# mcu.net
KiCad netlist of a schematic drawn in Altium Designer
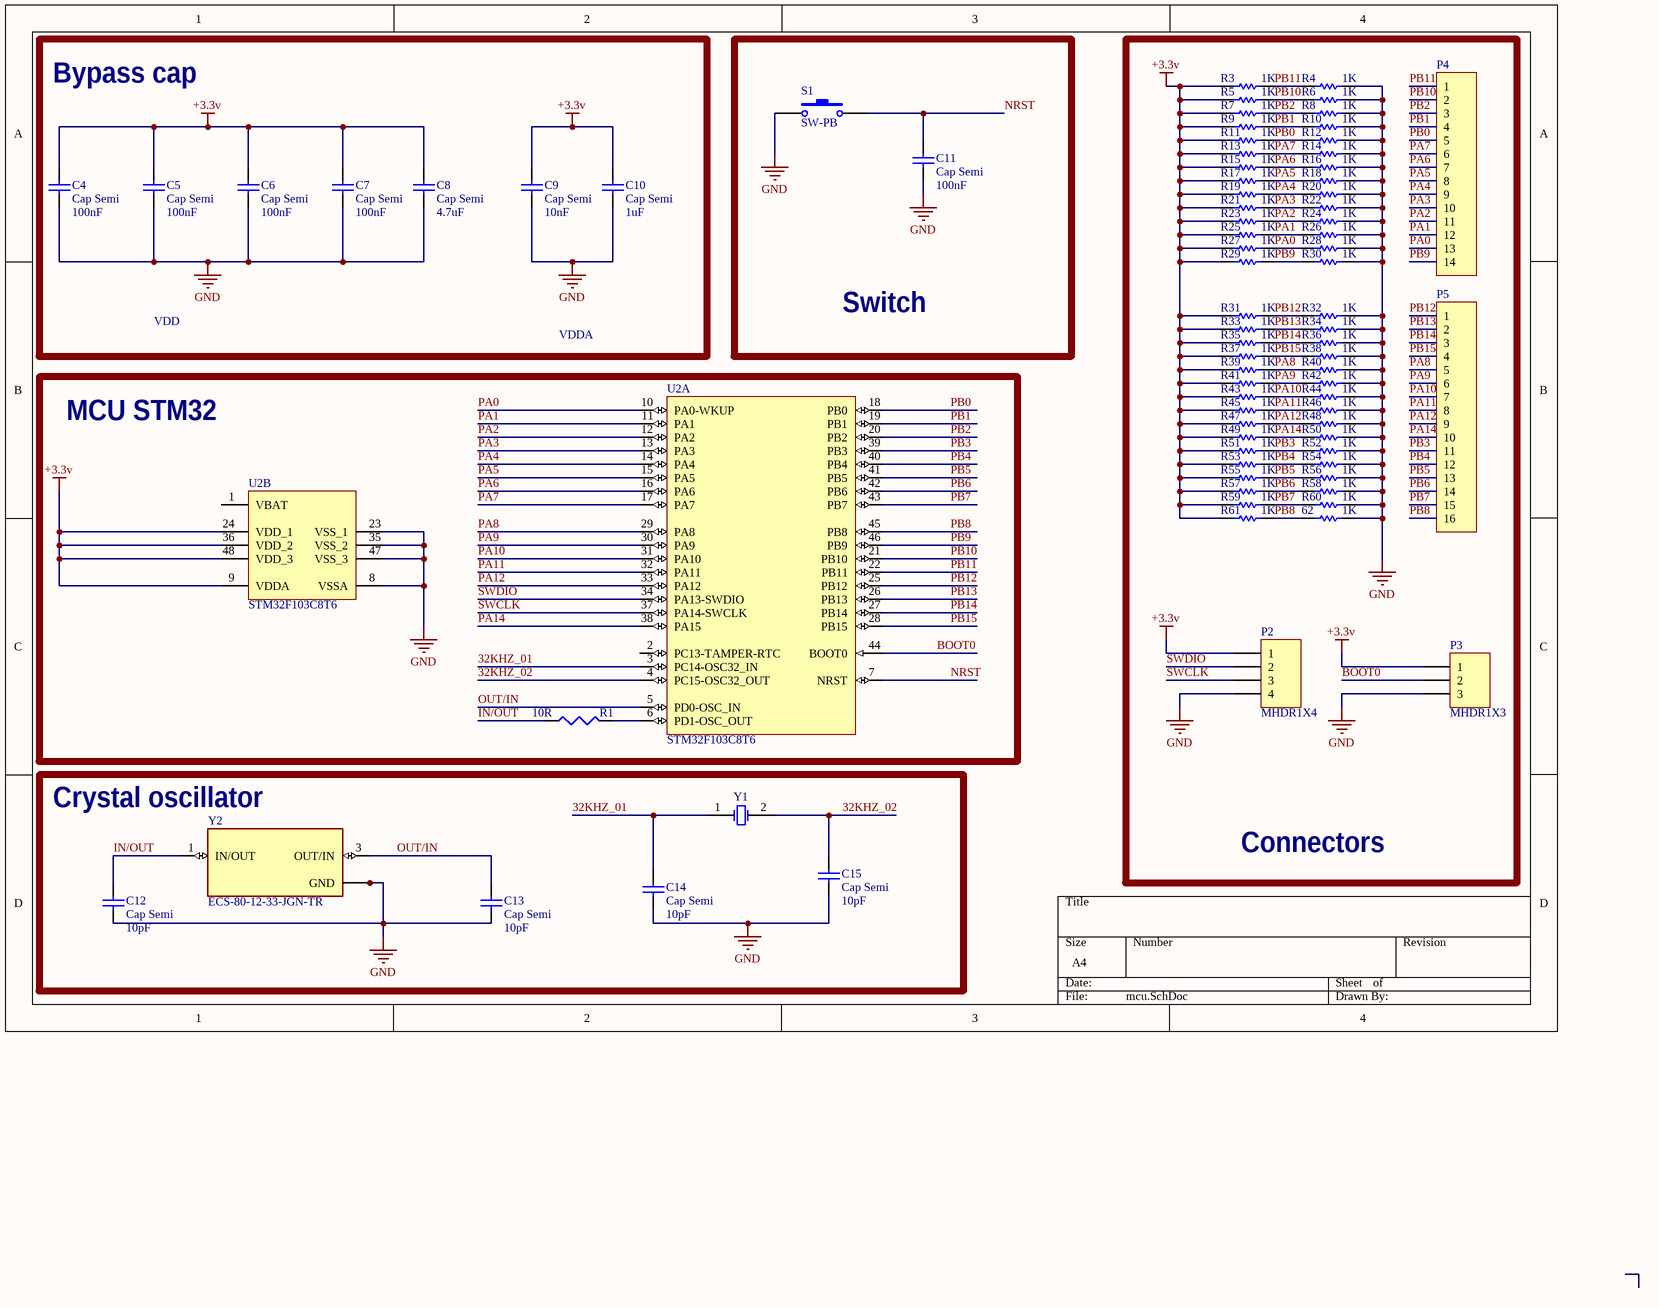
[diagram p0: mcu.SchDoc]

(export (version "E")
  (design (tool "Eeschema 10.0.6"))
  (components
    (comp (ref "62")
      (value "1K")
      (footprint "MY_0603")
      (description "Standard resistor")
      (fields (field (name "ASID PART NUMBER") "Res-AS"))
      (libsource (lib "1. Mylib Rev 4") (part "Res"))
    )
    (comp (ref "C4")
      (value "Cap Semi")
      (footprint "1608[0603]")
      (description "Capacitor (Semiconductor SIM Model)")
      (fields (field (name "ALTIUM_VALUE") "100nF") (field (name "PUBLISHER") "Altium Limited"))
      (libsource (lib "Miscellaneous Devices") (part "Cap Semi"))
    )
    (comp (ref "C5")
      (value "Cap Semi")
      (footprint "1608[0603]")
      (description "Capacitor (Semiconductor SIM Model)")
      (fields (field (name "ALTIUM_VALUE") "100nF") (field (name "PUBLISHER") "Altium Limited"))
      (libsource (lib "Miscellaneous Devices") (part "Cap Semi"))
    )
    (comp (ref "C6")
      (value "Cap Semi")
      (footprint "1608[0603]")
      (description "Capacitor (Semiconductor SIM Model)")
      (fields (field (name "ALTIUM_VALUE") "100nF") (field (name "PUBLISHER") "Altium Limited"))
      (libsource (lib "Miscellaneous Devices") (part "Cap Semi"))
    )
    (comp (ref "C7")
      (value "Cap Semi")
      (footprint "1608[0603]")
      (description "Capacitor (Semiconductor SIM Model)")
      (fields (field (name "ALTIUM_VALUE") "100nF") (field (name "PUBLISHER") "Altium Limited"))
      (libsource (lib "Miscellaneous Devices") (part "Cap Semi"))
    )
    (comp (ref "C8")
      (value "Cap Semi")
      (footprint "1608[0603]")
      (description "Capacitor (Semiconductor SIM Model)")
      (fields (field (name "ALTIUM_VALUE") "4.7uF") (field (name "PUBLISHER") "Altium Limited"))
      (libsource (lib "Miscellaneous Devices") (part "Cap Semi"))
    )
    (comp (ref "C9")
      (value "Cap Semi")
      (footprint "1608[0603]")
      (description "Capacitor (Semiconductor SIM Model)")
      (fields (field (name "ALTIUM_VALUE") "10nF") (field (name "PUBLISHER") "Altium Limited"))
      (libsource (lib "Miscellaneous Devices") (part "Cap Semi"))
    )
    (comp (ref "C10")
      (value "Cap Semi")
      (footprint "1608[0603]")
      (description "Capacitor (Semiconductor SIM Model)")
      (fields (field (name "ALTIUM_VALUE") "1uF") (field (name "PUBLISHER") "Altium Limited"))
      (libsource (lib "Miscellaneous Devices") (part "Cap Semi"))
    )
    (comp (ref "C11")
      (value "Cap Semi")
      (footprint "1608[0603]")
      (description "Capacitor (Semiconductor SIM Model)")
      (fields (field (name "ALTIUM_VALUE") "100nF") (field (name "PUBLISHER") "Altium Limited"))
      (libsource (lib "Miscellaneous Devices") (part "Cap Semi"))
    )
    (comp (ref "C12")
      (value "Cap Semi")
      (footprint "0402")
      (description "Capacitor (Semiconductor SIM Model)")
      (fields (field (name "ALTIUM_VALUE") "10pF") (field (name "PUBLISHER") "Altium Limited"))
      (libsource (lib "Miscellaneous Devices") (part "Cap Semi"))
    )
    (comp (ref "C13")
      (value "Cap Semi")
      (footprint "0402")
      (description "Capacitor (Semiconductor SIM Model)")
      (fields (field (name "ALTIUM_VALUE") "10pF") (field (name "PUBLISHER") "Altium Limited"))
      (libsource (lib "Miscellaneous Devices") (part "Cap Semi"))
    )
    (comp (ref "C14")
      (value "Cap Semi")
      (footprint "0402")
      (description "Capacitor (Semiconductor SIM Model)")
      (fields (field (name "ALTIUM_VALUE") "10pF") (field (name "PUBLISHER") "Altium Limited"))
      (libsource (lib "Miscellaneous Devices") (part "Cap Semi"))
    )
    (comp (ref "C15")
      (value "Cap Semi")
      (footprint "0402")
      (description "Capacitor (Semiconductor SIM Model)")
      (fields (field (name "ALTIUM_VALUE") "10pF") (field (name "PUBLISHER") "Altium Limited"))
      (libsource (lib "Miscellaneous Devices") (part "Cap Semi"))
    )
    (comp (ref "P2")
      (value "MHDR1X4")
      (footprint "MHDR1X4body")
      (description "Header, 4-Pin")
      (fields (field (name "PUBLISHER") "Altium Limited"))
      (libsource (lib "4. smartmcu") (part "MHDR1X4"))
    )
    (comp (ref "P3")
      (value "MHDR1X3")
      (footprint "MHDR1X3body")
      (description "Header, 3-Pin")
      (fields (field (name "PUBLISHER") "Altium Limited"))
      (libsource (lib "4. smartmcu") (part "MHDR1X3"))
    )
    (comp (ref "P4")
      (value "Header 14")
      (footprint "MY_FE14")
      (description "Header, 14-Pin")
      (fields (field (name "ASID PART NUMBER") "Header 14-AS"))
      (libsource (lib "1. Mylib Rev 4") (part "Header 14"))
    )
    (comp (ref "P5")
      (value "Header 16")
      (footprint "MY_FE16")
      (description "Header, 16-Pin")
      (fields (field (name "ASID PART NUMBER") "Header 16-AS"))
      (libsource (lib "1. Mylib Rev 4") (part "Header 16"))
    )
    (comp (ref "R1")
      (value "10R")
      (footprint "J1-0603")
      (description "Resistor")
      (fields (field (name "Comment") "Res3") (field (name "PUBLISHER") "Altium Limited"))
      (libsource (lib "Miscellaneous Devices") (part "Res3"))
    )
    (comp (ref "R3")
      (value "1K")
      (footprint "MY_0603")
      (description "Standard resistor")
      (fields (field (name "ASID PART NUMBER") "Res-AS"))
      (libsource (lib "1. Mylib Rev 4") (part "Res"))
    )
    (comp (ref "R4")
      (value "1K")
      (footprint "MY_0603")
      (description "Standard resistor")
      (fields (field (name "ASID PART NUMBER") "Res-AS"))
      (libsource (lib "1. Mylib Rev 4") (part "Res"))
    )
    (comp (ref "R5")
      (value "1K")
      (footprint "MY_0603")
      (description "Standard resistor")
      (fields (field (name "ASID PART NUMBER") "Res-AS"))
      (libsource (lib "1. Mylib Rev 4") (part "Res"))
    )
    (comp (ref "R6")
      (value "1K")
      (footprint "MY_0603")
      (description "Standard resistor")
      (fields (field (name "ASID PART NUMBER") "Res-AS"))
      (libsource (lib "1. Mylib Rev 4") (part "Res"))
    )
    (comp (ref "R7")
      (value "1K")
      (footprint "MY_0603")
      (description "Standard resistor")
      (fields (field (name "ASID PART NUMBER") "Res-AS"))
      (libsource (lib "1. Mylib Rev 4") (part "Res"))
    )
    (comp (ref "R8")
      (value "1K")
      (footprint "MY_0603")
      (description "Standard resistor")
      (fields (field (name "ASID PART NUMBER") "Res-AS"))
      (libsource (lib "1. Mylib Rev 4") (part "Res"))
    )
    (comp (ref "R9")
      (value "1K")
      (footprint "MY_0603")
      (description "Standard resistor")
      (fields (field (name "ASID PART NUMBER") "Res-AS"))
      (libsource (lib "1. Mylib Rev 4") (part "Res"))
    )
    (comp (ref "R10")
      (value "1K")
      (footprint "MY_0603")
      (description "Standard resistor")
      (fields (field (name "ASID PART NUMBER") "Res-AS"))
      (libsource (lib "1. Mylib Rev 4") (part "Res"))
    )
    (comp (ref "R11")
      (value "1K")
      (footprint "MY_0603")
      (description "Standard resistor")
      (fields (field (name "ASID PART NUMBER") "Res-AS"))
      (libsource (lib "1. Mylib Rev 4") (part "Res"))
    )
    (comp (ref "R12")
      (value "1K")
      (footprint "MY_0603")
      (description "Standard resistor")
      (fields (field (name "ASID PART NUMBER") "Res-AS"))
      (libsource (lib "1. Mylib Rev 4") (part "Res"))
    )
    (comp (ref "R13")
      (value "1K")
      (footprint "MY_0603")
      (description "Standard resistor")
      (fields (field (name "ASID PART NUMBER") "Res-AS"))
      (libsource (lib "1. Mylib Rev 4") (part "Res"))
    )
    (comp (ref "R14")
      (value "1K")
      (footprint "MY_0603")
      (description "Standard resistor")
      (fields (field (name "ASID PART NUMBER") "Res-AS"))
      (libsource (lib "1. Mylib Rev 4") (part "Res"))
    )
    (comp (ref "R15")
      (value "1K")
      (footprint "MY_0603")
      (description "Standard resistor")
      (fields (field (name "ASID PART NUMBER") "Res-AS"))
      (libsource (lib "1. Mylib Rev 4") (part "Res"))
    )
    (comp (ref "R16")
      (value "1K")
      (footprint "MY_0603")
      (description "Standard resistor")
      (fields (field (name "ASID PART NUMBER") "Res-AS"))
      (libsource (lib "1. Mylib Rev 4") (part "Res"))
    )
    (comp (ref "R17")
      (value "1K")
      (footprint "MY_0603")
      (description "Standard resistor")
      (fields (field (name "ASID PART NUMBER") "Res-AS"))
      (libsource (lib "1. Mylib Rev 4") (part "Res"))
    )
    (comp (ref "R18")
      (value "1K")
      (footprint "MY_0603")
      (description "Standard resistor")
      (fields (field (name "ASID PART NUMBER") "Res-AS"))
      (libsource (lib "1. Mylib Rev 4") (part "Res"))
    )
    (comp (ref "R19")
      (value "1K")
      (footprint "MY_0603")
      (description "Standard resistor")
      (fields (field (name "ASID PART NUMBER") "Res-AS"))
      (libsource (lib "1. Mylib Rev 4") (part "Res"))
    )
    (comp (ref "R20")
      (value "1K")
      (footprint "MY_0603")
      (description "Standard resistor")
      (fields (field (name "ASID PART NUMBER") "Res-AS"))
      (libsource (lib "1. Mylib Rev 4") (part "Res"))
    )
    (comp (ref "R21")
      (value "1K")
      (footprint "MY_0603")
      (description "Standard resistor")
      (fields (field (name "ASID PART NUMBER") "Res-AS"))
      (libsource (lib "1. Mylib Rev 4") (part "Res"))
    )
    (comp (ref "R22")
      (value "1K")
      (footprint "MY_0603")
      (description "Standard resistor")
      (fields (field (name "ASID PART NUMBER") "Res-AS"))
      (libsource (lib "1. Mylib Rev 4") (part "Res"))
    )
    (comp (ref "R23")
      (value "1K")
      (footprint "MY_0603")
      (description "Standard resistor")
      (fields (field (name "ASID PART NUMBER") "Res-AS"))
      (libsource (lib "1. Mylib Rev 4") (part "Res"))
    )
    (comp (ref "R24")
      (value "1K")
      (footprint "MY_0603")
      (description "Standard resistor")
      (fields (field (name "ASID PART NUMBER") "Res-AS"))
      (libsource (lib "1. Mylib Rev 4") (part "Res"))
    )
    (comp (ref "R25")
      (value "1K")
      (footprint "MY_0603")
      (description "Standard resistor")
      (fields (field (name "ASID PART NUMBER") "Res-AS"))
      (libsource (lib "1. Mylib Rev 4") (part "Res"))
    )
    (comp (ref "R26")
      (value "1K")
      (footprint "MY_0603")
      (description "Standard resistor")
      (fields (field (name "ASID PART NUMBER") "Res-AS"))
      (libsource (lib "1. Mylib Rev 4") (part "Res"))
    )
    (comp (ref "R27")
      (value "1K")
      (footprint "MY_0603")
      (description "Standard resistor")
      (fields (field (name "ASID PART NUMBER") "Res-AS"))
      (libsource (lib "1. Mylib Rev 4") (part "Res"))
    )
    (comp (ref "R28")
      (value "1K")
      (footprint "MY_0603")
      (description "Standard resistor")
      (fields (field (name "ASID PART NUMBER") "Res-AS"))
      (libsource (lib "1. Mylib Rev 4") (part "Res"))
    )
    (comp (ref "R29")
      (value "1K")
      (footprint "MY_0603")
      (description "Standard resistor")
      (fields (field (name "ASID PART NUMBER") "Res-AS"))
      (libsource (lib "1. Mylib Rev 4") (part "Res"))
    )
    (comp (ref "R30")
      (value "1K")
      (footprint "MY_0603")
      (description "Standard resistor")
      (fields (field (name "ASID PART NUMBER") "Res-AS"))
      (libsource (lib "1. Mylib Rev 4") (part "Res"))
    )
    (comp (ref "R31")
      (value "1K")
      (footprint "MY_0603")
      (description "Standard resistor")
      (fields (field (name "ASID PART NUMBER") "Res-AS"))
      (libsource (lib "1. Mylib Rev 4") (part "Res"))
    )
    (comp (ref "R32")
      (value "1K")
      (footprint "MY_0603")
      (description "Standard resistor")
      (fields (field (name "ASID PART NUMBER") "Res-AS"))
      (libsource (lib "1. Mylib Rev 4") (part "Res"))
    )
    (comp (ref "R33")
      (value "1K")
      (footprint "MY_0603")
      (description "Standard resistor")
      (fields (field (name "ASID PART NUMBER") "Res-AS"))
      (libsource (lib "1. Mylib Rev 4") (part "Res"))
    )
    (comp (ref "R34")
      (value "1K")
      (footprint "MY_0603")
      (description "Standard resistor")
      (fields (field (name "ASID PART NUMBER") "Res-AS"))
      (libsource (lib "1. Mylib Rev 4") (part "Res"))
    )
    (comp (ref "R35")
      (value "1K")
      (footprint "MY_0603")
      (description "Standard resistor")
      (fields (field (name "ASID PART NUMBER") "Res-AS"))
      (libsource (lib "1. Mylib Rev 4") (part "Res"))
    )
    (comp (ref "R36")
      (value "1K")
      (footprint "MY_0603")
      (description "Standard resistor")
      (fields (field (name "ASID PART NUMBER") "Res-AS"))
      (libsource (lib "1. Mylib Rev 4") (part "Res"))
    )
    (comp (ref "R37")
      (value "1K")
      (footprint "MY_0603")
      (description "Standard resistor")
      (fields (field (name "ASID PART NUMBER") "Res-AS"))
      (libsource (lib "1. Mylib Rev 4") (part "Res"))
    )
    (comp (ref "R38")
      (value "1K")
      (footprint "MY_0603")
      (description "Standard resistor")
      (fields (field (name "ASID PART NUMBER") "Res-AS"))
      (libsource (lib "1. Mylib Rev 4") (part "Res"))
    )
    (comp (ref "R39")
      (value "1K")
      (footprint "MY_0603")
      (description "Standard resistor")
      (fields (field (name "ASID PART NUMBER") "Res-AS"))
      (libsource (lib "1. Mylib Rev 4") (part "Res"))
    )
    (comp (ref "R40")
      (value "1K")
      (footprint "MY_0603")
      (description "Standard resistor")
      (fields (field (name "ASID PART NUMBER") "Res-AS"))
      (libsource (lib "1. Mylib Rev 4") (part "Res"))
    )
    (comp (ref "R41")
      (value "1K")
      (footprint "MY_0603")
      (description "Standard resistor")
      (fields (field (name "ASID PART NUMBER") "Res-AS"))
      (libsource (lib "1. Mylib Rev 4") (part "Res"))
    )
    (comp (ref "R42")
      (value "1K")
      (footprint "MY_0603")
      (description "Standard resistor")
      (fields (field (name "ASID PART NUMBER") "Res-AS"))
      (libsource (lib "1. Mylib Rev 4") (part "Res"))
    )
    (comp (ref "R43")
      (value "1K")
      (footprint "MY_0603")
      (description "Standard resistor")
      (fields (field (name "ASID PART NUMBER") "Res-AS"))
      (libsource (lib "1. Mylib Rev 4") (part "Res"))
    )
    (comp (ref "R44")
      (value "1K")
      (footprint "MY_0603")
      (description "Standard resistor")
      (fields (field (name "ASID PART NUMBER") "Res-AS"))
      (libsource (lib "1. Mylib Rev 4") (part "Res"))
    )
    (comp (ref "R45")
      (value "1K")
      (footprint "MY_0603")
      (description "Standard resistor")
      (fields (field (name "ASID PART NUMBER") "Res-AS"))
      (libsource (lib "1. Mylib Rev 4") (part "Res"))
    )
    (comp (ref "R46")
      (value "1K")
      (footprint "MY_0603")
      (description "Standard resistor")
      (fields (field (name "ASID PART NUMBER") "Res-AS"))
      (libsource (lib "1. Mylib Rev 4") (part "Res"))
    )
    (comp (ref "R47")
      (value "1K")
      (footprint "MY_0603")
      (description "Standard resistor")
      (fields (field (name "ASID PART NUMBER") "Res-AS"))
      (libsource (lib "1. Mylib Rev 4") (part "Res"))
    )
    (comp (ref "R48")
      (value "1K")
      (footprint "MY_0603")
      (description "Standard resistor")
      (fields (field (name "ASID PART NUMBER") "Res-AS"))
      (libsource (lib "1. Mylib Rev 4") (part "Res"))
    )
    (comp (ref "R49")
      (value "1K")
      (footprint "MY_0603")
      (description "Standard resistor")
      (fields (field (name "ASID PART NUMBER") "Res-AS"))
      (libsource (lib "1. Mylib Rev 4") (part "Res"))
    )
    (comp (ref "R50")
      (value "1K")
      (footprint "MY_0603")
      (description "Standard resistor")
      (fields (field (name "ASID PART NUMBER") "Res-AS"))
      (libsource (lib "1. Mylib Rev 4") (part "Res"))
    )
    (comp (ref "R51")
      (value "1K")
      (footprint "MY_0603")
      (description "Standard resistor")
      (fields (field (name "ASID PART NUMBER") "Res-AS"))
      (libsource (lib "1. Mylib Rev 4") (part "Res"))
    )
    (comp (ref "R52")
      (value "1K")
      (footprint "MY_0603")
      (description "Standard resistor")
      (fields (field (name "ASID PART NUMBER") "Res-AS"))
      (libsource (lib "1. Mylib Rev 4") (part "Res"))
    )
    (comp (ref "R53")
      (value "1K")
      (footprint "MY_0603")
      (description "Standard resistor")
      (fields (field (name "ASID PART NUMBER") "Res-AS"))
      (libsource (lib "1. Mylib Rev 4") (part "Res"))
    )
    (comp (ref "R54")
      (value "1K")
      (footprint "MY_0603")
      (description "Standard resistor")
      (fields (field (name "ASID PART NUMBER") "Res-AS"))
      (libsource (lib "1. Mylib Rev 4") (part "Res"))
    )
    (comp (ref "R55")
      (value "1K")
      (footprint "MY_0603")
      (description "Standard resistor")
      (fields (field (name "ASID PART NUMBER") "Res-AS"))
      (libsource (lib "1. Mylib Rev 4") (part "Res"))
    )
    (comp (ref "R56")
      (value "1K")
      (footprint "MY_0603")
      (description "Standard resistor")
      (fields (field (name "ASID PART NUMBER") "Res-AS"))
      (libsource (lib "1. Mylib Rev 4") (part "Res"))
    )
    (comp (ref "R57")
      (value "1K")
      (footprint "MY_0603")
      (description "Standard resistor")
      (fields (field (name "ASID PART NUMBER") "Res-AS"))
      (libsource (lib "1. Mylib Rev 4") (part "Res"))
    )
    (comp (ref "R58")
      (value "1K")
      (footprint "MY_0603")
      (description "Standard resistor")
      (fields (field (name "ASID PART NUMBER") "Res-AS"))
      (libsource (lib "1. Mylib Rev 4") (part "Res"))
    )
    (comp (ref "R59")
      (value "1K")
      (footprint "MY_0603")
      (description "Standard resistor")
      (fields (field (name "ASID PART NUMBER") "Res-AS"))
      (libsource (lib "1. Mylib Rev 4") (part "Res"))
    )
    (comp (ref "R60")
      (value "1K")
      (footprint "MY_0603")
      (description "Standard resistor")
      (fields (field (name "ASID PART NUMBER") "Res-AS"))
      (libsource (lib "1. Mylib Rev 4") (part "Res"))
    )
    (comp (ref "R61")
      (value "1K")
      (footprint "MY_0603")
      (description "Standard resistor")
      (fields (field (name "ASID PART NUMBER") "Res-AS"))
      (libsource (lib "1. Mylib Rev 4") (part "Res"))
    )
    (comp (ref "S1")
      (value "SW-PB")
      (footprint "SPST-2")
      (description "Switch")
      (fields (field (name "PUBLISHER") "Altium Limited"))
      (libsource (lib "Miscellaneous Devices") (part "SW-PB"))
    )
    (comp (ref "U2")
      (value "STM32F103C8T6")
      (footprint "STM-LQFP48_N")
      (libsource (lib "4. smartmcu") (part "STM32F103C8T6"))
    )
    (comp (ref "Y1")
      (value "~")
      (footprint "R38")
      (description "Crystal Oscillator")
      (fields (field (name "PUBLISHER") "Altium Limited"))
      (libsource (lib "Miscellaneous Devices") (part "XTAL"))
    )
    (comp (ref "Y2")
      (value "ECS-80-12-33-JGN-TR")
      (footprint "8MHZCrystall")
      (description "8MHz Â±20ppm Crystal 12pF 400 Ohms 4-SMD, No Lead")
      (fields
        (field (name "MF") "ECS Inc.")
        (field (name "BUYPART") "https://www.snapeda.com/parts/ECS-80-12-33-JGN-TR/ECS%20Inc./view-part/4477300/?ref=eda")
      )
      (libsource (lib "1. smartmcu") (part "ECS-80-12-33-JGN-TR"))
    )
  )
  (nets
    (net (code "1") (name "+3.3v") (class "Default")
      (node (ref "C10") (pin "2") (pinfunction "2_2") (pintype "passive"))
      (node (ref "C4") (pin "2") (pinfunction "2_2") (pintype "passive"))
      (node (ref "C5") (pin "2") (pinfunction "2_2") (pintype "passive"))
      (node (ref "C6") (pin "2") (pinfunction "2_2") (pintype "passive"))
      (node (ref "C7") (pin "2") (pinfunction "2_2") (pintype "passive"))
      (node (ref "C8") (pin "2") (pinfunction "2_2") (pintype "passive"))
      (node (ref "C9") (pin "2") (pinfunction "2_2") (pintype "passive"))
      (node (ref "P2") (pin "1") (pinfunction "1_1") (pintype "passive"))
      (node (ref "P3") (pin "1") (pinfunction "1_1") (pintype "passive"))
      (node (ref "R11") (pin "1") (pinfunction "1_1") (pintype "passive"))
      (node (ref "R13") (pin "1") (pinfunction "1_1") (pintype "passive"))
      (node (ref "R15") (pin "1") (pinfunction "1_1") (pintype "passive"))
      (node (ref "R17") (pin "1") (pinfunction "1_1") (pintype "passive"))
      (node (ref "R19") (pin "1") (pinfunction "1_1") (pintype "passive"))
      (node (ref "R21") (pin "1") (pinfunction "1_1") (pintype "passive"))
      (node (ref "R23") (pin "1") (pinfunction "1_1") (pintype "passive"))
      (node (ref "R25") (pin "1") (pinfunction "1_1") (pintype "passive"))
      (node (ref "R27") (pin "1") (pinfunction "1_1") (pintype "passive"))
      (node (ref "R29") (pin "1") (pinfunction "1_1") (pintype "passive"))
      (node (ref "R3") (pin "1") (pinfunction "1_1") (pintype "passive"))
      (node (ref "R31") (pin "1") (pinfunction "1_1") (pintype "passive"))
      (node (ref "R33") (pin "1") (pinfunction "1_1") (pintype "passive"))
      (node (ref "R35") (pin "1") (pinfunction "1_1") (pintype "passive"))
      (node (ref "R37") (pin "1") (pinfunction "1_1") (pintype "passive"))
      (node (ref "R39") (pin "1") (pinfunction "1_1") (pintype "passive"))
      (node (ref "R41") (pin "1") (pinfunction "1_1") (pintype "passive"))
      (node (ref "R43") (pin "1") (pinfunction "1_1") (pintype "passive"))
      (node (ref "R45") (pin "1") (pinfunction "1_1") (pintype "passive"))
      (node (ref "R47") (pin "1") (pinfunction "1_1") (pintype "passive"))
      (node (ref "R49") (pin "1") (pinfunction "1_1") (pintype "passive"))
      (node (ref "R5") (pin "1") (pinfunction "1_1") (pintype "passive"))
      (node (ref "R51") (pin "1") (pinfunction "1_1") (pintype "passive"))
      (node (ref "R53") (pin "1") (pinfunction "1_1") (pintype "passive"))
      (node (ref "R55") (pin "1") (pinfunction "1_1") (pintype "passive"))
      (node (ref "R57") (pin "1") (pinfunction "1_1") (pintype "passive"))
      (node (ref "R59") (pin "1") (pinfunction "1_1") (pintype "passive"))
      (node (ref "R61") (pin "1") (pinfunction "1_1") (pintype "passive"))
      (node (ref "R7") (pin "1") (pinfunction "1_1") (pintype "passive"))
      (node (ref "R9") (pin "1") (pinfunction "1_1") (pintype "passive"))
      (node (ref "U2") (pin "24") (pinfunction "VDD_1_24") (pintype "power_in"))
      (node (ref "U2") (pin "36") (pinfunction "VDD_2_36") (pintype "power_in"))
      (node (ref "U2") (pin "48") (pinfunction "VDD_3_48") (pintype "power_in"))
      (node (ref "U2") (pin "9") (pinfunction "VDDA_9") (pintype "power_in"))
    )
    (net (code "2") (name "/32KHZ_01") (class "Default")
      (node (ref "C14") (pin "2") (pinfunction "2_2") (pintype "passive"))
      (node (ref "U2") (pin "3") (pinfunction "PC14-OSC32_IN_3") (pintype "bidirectional"))
      (node (ref "Y1") (pin "1") (pinfunction "OSC1_1") (pintype "passive"))
    )
    (net (code "3") (name "/32KHZ_02") (class "Default")
      (node (ref "C15") (pin "2") (pinfunction "2_2") (pintype "passive"))
      (node (ref "U2") (pin "4") (pinfunction "PC15-OSC32_OUT_4") (pintype "bidirectional"))
      (node (ref "Y1") (pin "2") (pinfunction "OSC2_2") (pintype "passive"))
    )
    (net (code "4") (name "/BOOT0") (class "Default")
      (node (ref "P3") (pin "2") (pinfunction "2_2") (pintype "passive"))
      (node (ref "U2") (pin "44") (pinfunction "BOOT0_44") (pintype "input"))
    )
    (net (code "5") (name "/IN{slash}OUT") (class "Default")
      (node (ref "C12") (pin "2") (pinfunction "2_2") (pintype "passive"))
      (node (ref "R1") (pin "1") (pinfunction "1_1") (pintype "passive"))
      (node (ref "Y2") (pin "1") (pinfunction "IN/OUT_1") (pintype "bidirectional"))
    )
    (net (code "6") (name "/NRST") (class "Default")
      (node (ref "C11") (pin "2") (pinfunction "2_2") (pintype "passive"))
      (node (ref "S1") (pin "2") (pinfunction "2_2") (pintype "passive"))
      (node (ref "U2") (pin "7") (pinfunction "NRST_7") (pintype "bidirectional"))
    )
    (net (code "7") (name "/OUT{slash}IN") (class "Default")
      (node (ref "C13") (pin "2") (pinfunction "2_2") (pintype "passive"))
      (node (ref "U2") (pin "5") (pinfunction "PD0-OSC_IN_5") (pintype "bidirectional"))
      (node (ref "Y2") (pin "3") (pinfunction "OUT/IN_3") (pintype "bidirectional"))
    )
    (net (code "8") (name "/PA0") (class "Default")
      (node (ref "P4") (pin "13") (pinfunction "13_13") (pintype "passive"))
      (node (ref "R27") (pin "2") (pinfunction "2_2") (pintype "passive"))
      (node (ref "R28") (pin "1") (pinfunction "1_1") (pintype "passive"))
      (node (ref "U2") (pin "10") (pinfunction "PA0-WKUP_10") (pintype "bidirectional"))
    )
    (net (code "9") (name "/PA1") (class "Default")
      (node (ref "P4") (pin "12") (pinfunction "12_12") (pintype "passive"))
      (node (ref "R25") (pin "2") (pinfunction "2_2") (pintype "passive"))
      (node (ref "R26") (pin "1") (pinfunction "1_1") (pintype "passive"))
      (node (ref "U2") (pin "11") (pinfunction "PA1_11") (pintype "bidirectional"))
    )
    (net (code "10") (name "/PA2") (class "Default")
      (node (ref "P4") (pin "11") (pinfunction "11_11") (pintype "passive"))
      (node (ref "R23") (pin "2") (pinfunction "2_2") (pintype "passive"))
      (node (ref "R24") (pin "1") (pinfunction "1_1") (pintype "passive"))
      (node (ref "U2") (pin "12") (pinfunction "PA2_12") (pintype "bidirectional"))
    )
    (net (code "11") (name "/PA3") (class "Default")
      (node (ref "P4") (pin "10") (pinfunction "10_10") (pintype "passive"))
      (node (ref "R21") (pin "2") (pinfunction "2_2") (pintype "passive"))
      (node (ref "R22") (pin "1") (pinfunction "1_1") (pintype "passive"))
      (node (ref "U2") (pin "13") (pinfunction "PA3_13") (pintype "bidirectional"))
    )
    (net (code "12") (name "/PA4") (class "Default")
      (node (ref "P4") (pin "9") (pinfunction "9_9") (pintype "passive"))
      (node (ref "R19") (pin "2") (pinfunction "2_2") (pintype "passive"))
      (node (ref "R20") (pin "1") (pinfunction "1_1") (pintype "passive"))
      (node (ref "U2") (pin "14") (pinfunction "PA4_14") (pintype "bidirectional"))
    )
    (net (code "13") (name "/PA5") (class "Default")
      (node (ref "P4") (pin "8") (pinfunction "8_8") (pintype "passive"))
      (node (ref "R17") (pin "2") (pinfunction "2_2") (pintype "passive"))
      (node (ref "R18") (pin "1") (pinfunction "1_1") (pintype "passive"))
      (node (ref "U2") (pin "15") (pinfunction "PA5_15") (pintype "bidirectional"))
    )
    (net (code "14") (name "/PA6") (class "Default")
      (node (ref "P4") (pin "7") (pinfunction "7_7") (pintype "passive"))
      (node (ref "R15") (pin "2") (pinfunction "2_2") (pintype "passive"))
      (node (ref "R16") (pin "1") (pinfunction "1_1") (pintype "passive"))
      (node (ref "U2") (pin "16") (pinfunction "PA6_16") (pintype "bidirectional"))
    )
    (net (code "15") (name "/PA7") (class "Default")
      (node (ref "P4") (pin "6") (pinfunction "6_6") (pintype "passive"))
      (node (ref "R13") (pin "2") (pinfunction "2_2") (pintype "passive"))
      (node (ref "R14") (pin "1") (pinfunction "1_1") (pintype "passive"))
      (node (ref "U2") (pin "17") (pinfunction "PA7_17") (pintype "bidirectional"))
    )
    (net (code "16") (name "/PA8") (class "Default")
      (node (ref "P5") (pin "5") (pinfunction "5_5") (pintype "passive"))
      (node (ref "R39") (pin "2") (pinfunction "2_2") (pintype "passive"))
      (node (ref "R40") (pin "1") (pinfunction "1_1") (pintype "passive"))
      (node (ref "U2") (pin "29") (pinfunction "PA8_29") (pintype "bidirectional"))
    )
    (net (code "17") (name "/PA9") (class "Default")
      (node (ref "P5") (pin "6") (pinfunction "6_6") (pintype "passive"))
      (node (ref "R41") (pin "2") (pinfunction "2_2") (pintype "passive"))
      (node (ref "R42") (pin "1") (pinfunction "1_1") (pintype "passive"))
      (node (ref "U2") (pin "30") (pinfunction "PA9_30") (pintype "bidirectional"))
    )
    (net (code "18") (name "/PA10") (class "Default")
      (node (ref "P5") (pin "7") (pinfunction "7_7") (pintype "passive"))
      (node (ref "R43") (pin "2") (pinfunction "2_2") (pintype "passive"))
      (node (ref "R44") (pin "1") (pinfunction "1_1") (pintype "passive"))
      (node (ref "U2") (pin "31") (pinfunction "PA10_31") (pintype "bidirectional"))
    )
    (net (code "19") (name "/PA11") (class "Default")
      (node (ref "P5") (pin "8") (pinfunction "8_8") (pintype "passive"))
      (node (ref "R45") (pin "2") (pinfunction "2_2") (pintype "passive"))
      (node (ref "R46") (pin "1") (pinfunction "1_1") (pintype "passive"))
      (node (ref "U2") (pin "32") (pinfunction "PA11_32") (pintype "bidirectional"))
    )
    (net (code "20") (name "/PA12") (class "Default")
      (node (ref "P5") (pin "9") (pinfunction "9_9") (pintype "passive"))
      (node (ref "R47") (pin "2") (pinfunction "2_2") (pintype "passive"))
      (node (ref "R48") (pin "1") (pinfunction "1_1") (pintype "passive"))
      (node (ref "U2") (pin "33") (pinfunction "PA12_33") (pintype "bidirectional"))
    )
    (net (code "21") (name "/PA14") (class "Default")
      (node (ref "P5") (pin "10") (pinfunction "10_10") (pintype "passive"))
      (node (ref "R49") (pin "2") (pinfunction "2_2") (pintype "passive"))
      (node (ref "R50") (pin "1") (pinfunction "1_1") (pintype "passive"))
      (node (ref "U2") (pin "38") (pinfunction "PA15_38") (pintype "bidirectional"))
    )
    (net (code "22") (name "/PB0") (class "Default")
      (node (ref "P4") (pin "5") (pinfunction "5_5") (pintype "passive"))
      (node (ref "R11") (pin "2") (pinfunction "2_2") (pintype "passive"))
      (node (ref "R12") (pin "1") (pinfunction "1_1") (pintype "passive"))
      (node (ref "U2") (pin "18") (pinfunction "PB0_18") (pintype "bidirectional"))
    )
    (net (code "23") (name "/PB1") (class "Default")
      (node (ref "P4") (pin "4") (pinfunction "4_4") (pintype "passive"))
      (node (ref "R10") (pin "1") (pinfunction "1_1") (pintype "passive"))
      (node (ref "R9") (pin "2") (pinfunction "2_2") (pintype "passive"))
      (node (ref "U2") (pin "19") (pinfunction "PB1_19") (pintype "bidirectional"))
    )
    (net (code "24") (name "/PB2") (class "Default")
      (node (ref "P4") (pin "3") (pinfunction "3_3") (pintype "passive"))
      (node (ref "R7") (pin "2") (pinfunction "2_2") (pintype "passive"))
      (node (ref "R8") (pin "1") (pinfunction "1_1") (pintype "passive"))
      (node (ref "U2") (pin "20") (pinfunction "PB2_20") (pintype "bidirectional"))
    )
    (net (code "25") (name "/PB3") (class "Default")
      (node (ref "P5") (pin "11") (pinfunction "11_11") (pintype "passive"))
      (node (ref "R51") (pin "2") (pinfunction "2_2") (pintype "passive"))
      (node (ref "R52") (pin "1") (pinfunction "1_1") (pintype "passive"))
      (node (ref "U2") (pin "39") (pinfunction "PB3_39") (pintype "bidirectional"))
    )
    (net (code "26") (name "/PB4") (class "Default")
      (node (ref "P5") (pin "12") (pinfunction "12_12") (pintype "passive"))
      (node (ref "R53") (pin "2") (pinfunction "2_2") (pintype "passive"))
      (node (ref "R54") (pin "1") (pinfunction "1_1") (pintype "passive"))
      (node (ref "U2") (pin "40") (pinfunction "PB4_40") (pintype "bidirectional"))
    )
    (net (code "27") (name "/PB5") (class "Default")
      (node (ref "P5") (pin "13") (pinfunction "13_13") (pintype "passive"))
      (node (ref "R55") (pin "2") (pinfunction "2_2") (pintype "passive"))
      (node (ref "R56") (pin "1") (pinfunction "1_1") (pintype "passive"))
      (node (ref "U2") (pin "41") (pinfunction "PB5_41") (pintype "bidirectional"))
    )
    (net (code "28") (name "/PB6") (class "Default")
      (node (ref "P5") (pin "14") (pinfunction "14_14") (pintype "passive"))
      (node (ref "R57") (pin "2") (pinfunction "2_2") (pintype "passive"))
      (node (ref "R58") (pin "1") (pinfunction "1_1") (pintype "passive"))
      (node (ref "U2") (pin "42") (pinfunction "PB6_42") (pintype "bidirectional"))
    )
    (net (code "29") (name "/PB7") (class "Default")
      (node (ref "P5") (pin "15") (pinfunction "15_15") (pintype "passive"))
      (node (ref "R59") (pin "2") (pinfunction "2_2") (pintype "passive"))
      (node (ref "R60") (pin "1") (pinfunction "1_1") (pintype "passive"))
      (node (ref "U2") (pin "43") (pinfunction "PB7_43") (pintype "bidirectional"))
    )
    (net (code "30") (name "/PB8") (class "Default")
      (node (ref "62") (pin "1") (pinfunction "1_1") (pintype "passive"))
      (node (ref "P5") (pin "16") (pinfunction "16_16") (pintype "passive"))
      (node (ref "R61") (pin "2") (pinfunction "2_2") (pintype "passive"))
      (node (ref "U2") (pin "45") (pinfunction "PB8_45") (pintype "bidirectional"))
    )
    (net (code "31") (name "/PB9") (class "Default")
      (node (ref "P4") (pin "14") (pinfunction "14_14") (pintype "passive"))
      (node (ref "R29") (pin "2") (pinfunction "2_2") (pintype "passive"))
      (node (ref "R30") (pin "1") (pinfunction "1_1") (pintype "passive"))
      (node (ref "U2") (pin "46") (pinfunction "PB9_46") (pintype "bidirectional"))
    )
    (net (code "32") (name "/PB10") (class "Default")
      (node (ref "P4") (pin "2") (pinfunction "2_2") (pintype "passive"))
      (node (ref "R5") (pin "2") (pinfunction "2_2") (pintype "passive"))
      (node (ref "R6") (pin "1") (pinfunction "1_1") (pintype "passive"))
      (node (ref "U2") (pin "21") (pinfunction "PB10_21") (pintype "bidirectional"))
    )
    (net (code "33") (name "/PB11") (class "Default")
      (node (ref "P4") (pin "1") (pinfunction "1_1") (pintype "passive"))
      (node (ref "R3") (pin "2") (pinfunction "2_2") (pintype "passive"))
      (node (ref "R4") (pin "1") (pinfunction "1_1") (pintype "passive"))
      (node (ref "U2") (pin "22") (pinfunction "PB11_22") (pintype "bidirectional"))
    )
    (net (code "34") (name "/PB12") (class "Default")
      (node (ref "P5") (pin "1") (pinfunction "1_1") (pintype "passive"))
      (node (ref "R31") (pin "2") (pinfunction "2_2") (pintype "passive"))
      (node (ref "R32") (pin "1") (pinfunction "1_1") (pintype "passive"))
      (node (ref "U2") (pin "25") (pinfunction "PB12_25") (pintype "bidirectional"))
    )
    (net (code "35") (name "/PB13") (class "Default")
      (node (ref "P5") (pin "2") (pinfunction "2_2") (pintype "passive"))
      (node (ref "R33") (pin "2") (pinfunction "2_2") (pintype "passive"))
      (node (ref "R34") (pin "1") (pinfunction "1_1") (pintype "passive"))
      (node (ref "U2") (pin "26") (pinfunction "PB13_26") (pintype "bidirectional"))
    )
    (net (code "36") (name "/PB14") (class "Default")
      (node (ref "P5") (pin "3") (pinfunction "3_3") (pintype "passive"))
      (node (ref "R35") (pin "2") (pinfunction "2_2") (pintype "passive"))
      (node (ref "R36") (pin "1") (pinfunction "1_1") (pintype "passive"))
      (node (ref "U2") (pin "27") (pinfunction "PB14_27") (pintype "bidirectional"))
    )
    (net (code "37") (name "/PB15") (class "Default")
      (node (ref "P5") (pin "4") (pinfunction "4_4") (pintype "passive"))
      (node (ref "R37") (pin "2") (pinfunction "2_2") (pintype "passive"))
      (node (ref "R38") (pin "1") (pinfunction "1_1") (pintype "passive"))
      (node (ref "U2") (pin "28") (pinfunction "PB15_28") (pintype "bidirectional"))
    )
    (net (code "38") (name "/SWCLK") (class "Default")
      (node (ref "P2") (pin "3") (pinfunction "3_3") (pintype "passive"))
      (node (ref "U2") (pin "37") (pinfunction "PA14-SWCLK_37") (pintype "bidirectional"))
    )
    (net (code "39") (name "/SWDIO") (class "Default")
      (node (ref "P2") (pin "2") (pinfunction "2_2") (pintype "passive"))
      (node (ref "U2") (pin "34") (pinfunction "PA13-SWDIO_34") (pintype "bidirectional"))
    )
    (net (code "40") (name "GND") (class "Default")
      (node (ref "62") (pin "2") (pinfunction "2_2") (pintype "passive"))
      (node (ref "C10") (pin "1") (pinfunction "1_1") (pintype "passive"))
      (node (ref "C11") (pin "1") (pinfunction "1_1") (pintype "passive"))
      (node (ref "C12") (pin "1") (pinfunction "1_1") (pintype "passive"))
      (node (ref "C13") (pin "1") (pinfunction "1_1") (pintype "passive"))
      (node (ref "C14") (pin "1") (pinfunction "1_1") (pintype "passive"))
      (node (ref "C15") (pin "1") (pinfunction "1_1") (pintype "passive"))
      (node (ref "C4") (pin "1") (pinfunction "1_1") (pintype "passive"))
      (node (ref "C5") (pin "1") (pinfunction "1_1") (pintype "passive"))
      (node (ref "C6") (pin "1") (pinfunction "1_1") (pintype "passive"))
      (node (ref "C7") (pin "1") (pinfunction "1_1") (pintype "passive"))
      (node (ref "C8") (pin "1") (pinfunction "1_1") (pintype "passive"))
      (node (ref "C9") (pin "1") (pinfunction "1_1") (pintype "passive"))
      (node (ref "P2") (pin "4") (pinfunction "4_4") (pintype "passive"))
      (node (ref "P3") (pin "3") (pinfunction "3_3") (pintype "passive"))
      (node (ref "R10") (pin "2") (pinfunction "2_2") (pintype "passive"))
      (node (ref "R12") (pin "2") (pinfunction "2_2") (pintype "passive"))
      (node (ref "R14") (pin "2") (pinfunction "2_2") (pintype "passive"))
      (node (ref "R16") (pin "2") (pinfunction "2_2") (pintype "passive"))
      (node (ref "R18") (pin "2") (pinfunction "2_2") (pintype "passive"))
      (node (ref "R20") (pin "2") (pinfunction "2_2") (pintype "passive"))
      (node (ref "R22") (pin "2") (pinfunction "2_2") (pintype "passive"))
      (node (ref "R24") (pin "2") (pinfunction "2_2") (pintype "passive"))
      (node (ref "R26") (pin "2") (pinfunction "2_2") (pintype "passive"))
      (node (ref "R28") (pin "2") (pinfunction "2_2") (pintype "passive"))
      (node (ref "R30") (pin "2") (pinfunction "2_2") (pintype "passive"))
      (node (ref "R32") (pin "2") (pinfunction "2_2") (pintype "passive"))
      (node (ref "R34") (pin "2") (pinfunction "2_2") (pintype "passive"))
      (node (ref "R36") (pin "2") (pinfunction "2_2") (pintype "passive"))
      (node (ref "R38") (pin "2") (pinfunction "2_2") (pintype "passive"))
      (node (ref "R4") (pin "2") (pinfunction "2_2") (pintype "passive"))
      (node (ref "R40") (pin "2") (pinfunction "2_2") (pintype "passive"))
      (node (ref "R42") (pin "2") (pinfunction "2_2") (pintype "passive"))
      (node (ref "R44") (pin "2") (pinfunction "2_2") (pintype "passive"))
      (node (ref "R46") (pin "2") (pinfunction "2_2") (pintype "passive"))
      (node (ref "R48") (pin "2") (pinfunction "2_2") (pintype "passive"))
      (node (ref "R50") (pin "2") (pinfunction "2_2") (pintype "passive"))
      (node (ref "R52") (pin "2") (pinfunction "2_2") (pintype "passive"))
      (node (ref "R54") (pin "2") (pinfunction "2_2") (pintype "passive"))
      (node (ref "R56") (pin "2") (pinfunction "2_2") (pintype "passive"))
      (node (ref "R58") (pin "2") (pinfunction "2_2") (pintype "passive"))
      (node (ref "R6") (pin "2") (pinfunction "2_2") (pintype "passive"))
      (node (ref "R60") (pin "2") (pinfunction "2_2") (pintype "passive"))
      (node (ref "R8") (pin "2") (pinfunction "2_2") (pintype "passive"))
      (node (ref "S1") (pin "1") (pinfunction "1_1") (pintype "passive"))
      (node (ref "U2") (pin "23") (pinfunction "VSS_1_23") (pintype "power_in"))
      (node (ref "U2") (pin "35") (pinfunction "VSS_2_35") (pintype "power_in"))
      (node (ref "U2") (pin "47") (pinfunction "VSS_3_47") (pintype "power_in"))
      (node (ref "U2") (pin "8") (pinfunction "VSSA_8") (pintype "power_in"))
      (node (ref "Y2") (pin "2") (pinfunction "GND_2") (pintype "power_in"))
      (node (ref "Y2") (pin "4") (pinfunction "GND_4") (pintype "power_in"))
    )
    (net (code "41") (name "Net-(U2A-PD1-OSC_OUT)") (class "Default")
      (node (ref "R1") (pin "2") (pinfunction "2_2") (pintype "passive"))
      (node (ref "U2") (pin "6") (pinfunction "PD1-OSC_OUT_6") (pintype "bidirectional"))
    )
    (net (code "42") (name "unconnected-(U2A-PC13-TAMPER-RTC-Pad2)") (class "Default")
      (node (ref "U2") (pin "2") (pinfunction "PC13-TAMPER-RTC_2") (pintype "bidirectional"))
    )
    (net (code "43") (name "unconnected-(U2B-VBAT-Pad1)") (class "Default")
      (node (ref "U2") (pin "1") (pinfunction "VBAT_1") (pintype "power_in"))
    )
  )
)
